# Main.net
KiCad netlist of a schematic drawn in Altium Designer
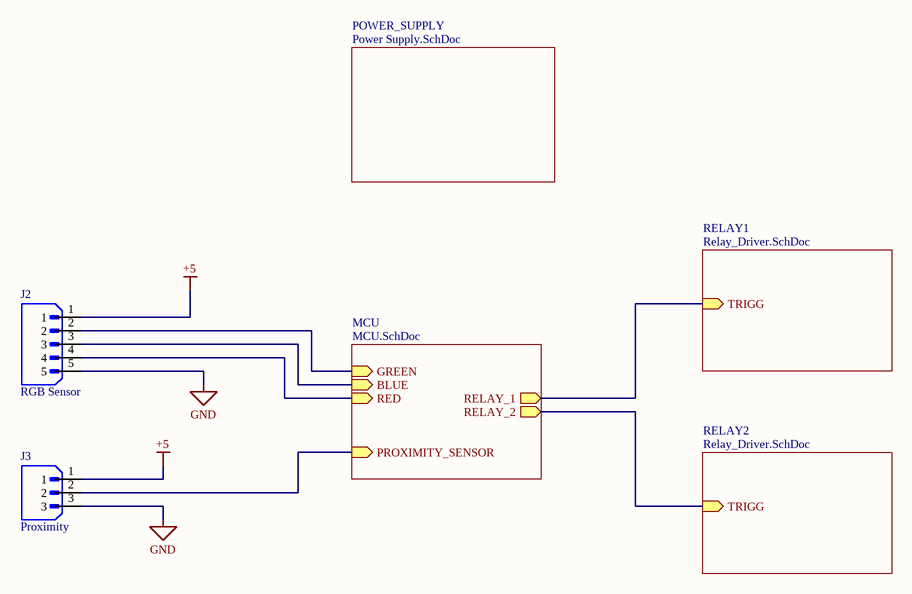
[diagram p0: Main.SchDoc]

(export (version "E")
  (design (tool "Eeschema 10.0.6"))
  (components
    (comp (ref "J2")
      (value "RGB Sensor")
      (footprint "JST_B5B-XH-A(LF)(SN)")
      (description "Connector Header Through Hole 5 position 0.098 (2.50mm)")
      (fields (field (name "MF") "JST Sales America Inc.") (field (name "MP") "B5B-XH-A(LF)(SN)"))
      (libsource (lib "B5B-XH-A_LF__SN_") (part "B5B-XH-A(LF)(SN)"))
    )
    (comp (ref "J3")
      (value "Proximity")
      (footprint "JST_B3B-XH-A (LF)(SN)")
      (description "Connector Header Through Hole 3 position 0.098 (2.50mm)")
      (fields (field (name "MF") "JST Sales America Inc.") (field (name "MP") "B3B-XH-A (LF)(SN)"))
      (libsource (lib "B3B-XH-A__LF__SN_") (part "B3B-XH-A_(LF)(SN)"))
    )
  )
  (nets
    (net (code "1") (name "+5") (class "Default")
      (node (ref "J2") (pin "1") (pinfunction "1_1") (pintype "passive"))
      (node (ref "J3") (pin "1") (pinfunction "1_1") (pintype "passive"))
    )
    (net (code "2") (name "/BLUE") (class "Default")
      (node (ref "J2") (pin "3") (pinfunction "3_3") (pintype "passive"))
    )
    (net (code "3") (name "/GREEN") (class "Default")
      (node (ref "J2") (pin "2") (pinfunction "2_2") (pintype "passive"))
    )
    (net (code "4") (name "/PROXIMITY_SENSOR") (class "Default")
      (node (ref "J3") (pin "2") (pinfunction "2_2") (pintype "passive"))
    )
    (net (code "5") (name "/RED") (class "Default")
      (node (ref "J2") (pin "4") (pinfunction "4_4") (pintype "passive"))
    )
    (net (code "8") (name "GND") (class "Default")
      (node (ref "J2") (pin "5") (pinfunction "5_5") (pintype "passive"))
      (node (ref "J3") (pin "3") (pinfunction "3_3") (pintype "passive"))
    )
  )
)
